# DiveComputer_TFT18.net
KiCad netlist of a schematic drawn in EAGLE
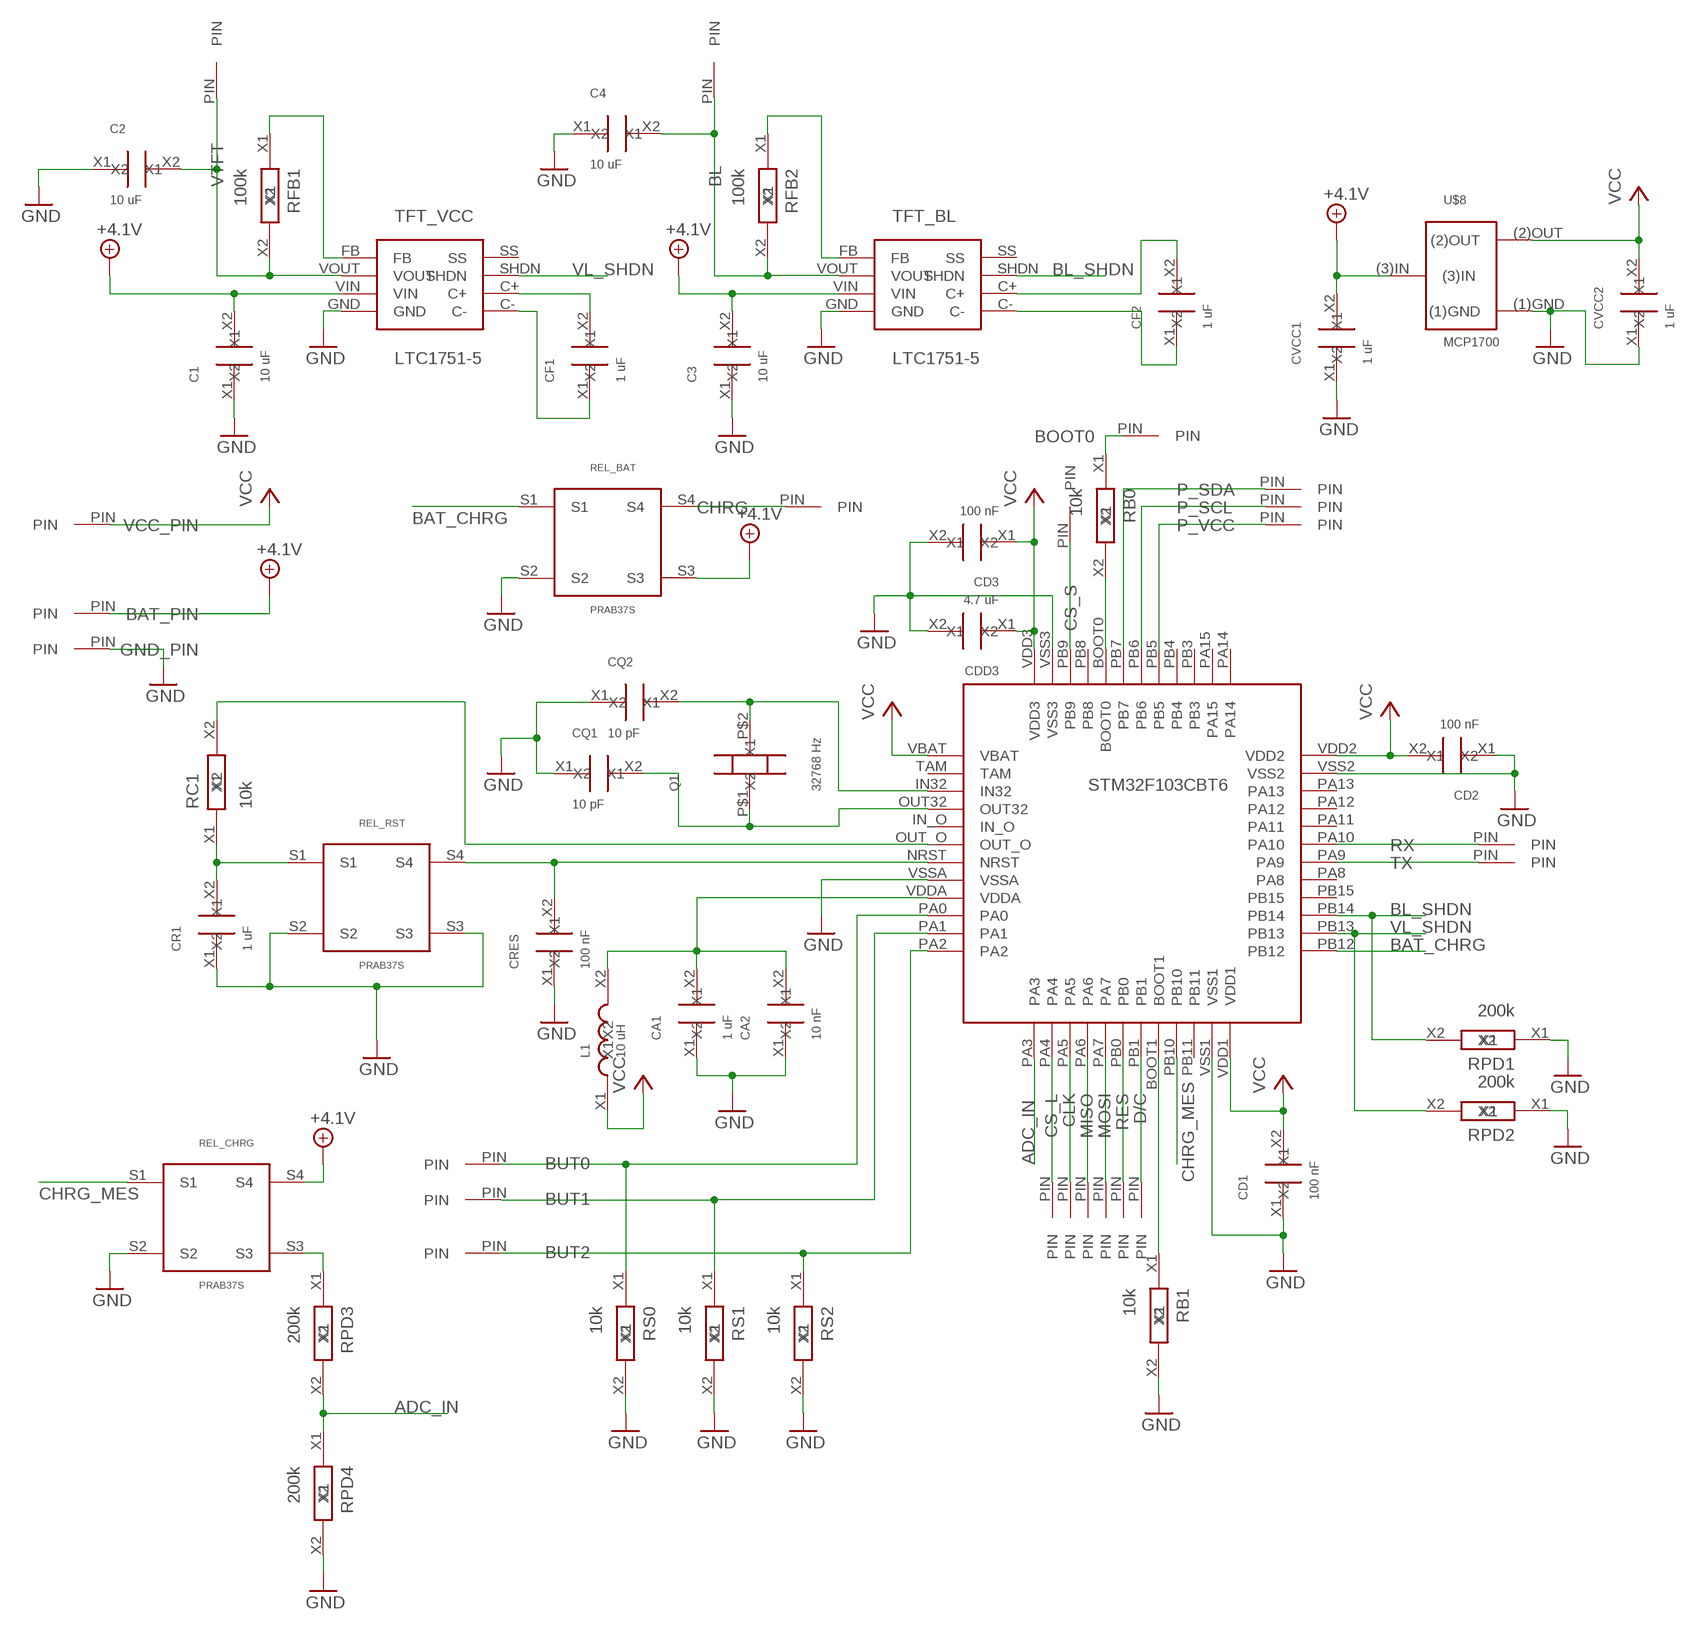
[diagram p0: schematic, sheet 1]

(export (version "E")
  (design (tool "Eeschema 10.0.6"))
  (components
    (comp (ref "BAT_PIN")
      (value "PIN_06")
      (footprint "eagle-import:PIN_06")
      (libsource (lib "eagle-import") (part "PIN_06"))
    )
    (comp (ref "BL")
      (value "PIN_06")
      (footprint "eagle-import:PIN_06")
      (libsource (lib "eagle-import") (part "PIN_06"))
    )
    (comp (ref "BOOT0")
      (value "PIN_06")
      (footprint "eagle-import:PIN_06")
      (libsource (lib "eagle-import") (part "PIN_06"))
    )
    (comp (ref "BUT0")
      (value "PIN_06")
      (footprint "eagle-import:PIN_06")
      (libsource (lib "eagle-import") (part "PIN_06"))
    )
    (comp (ref "BUT1")
      (value "PIN_06")
      (footprint "eagle-import:PIN_06")
      (libsource (lib "eagle-import") (part "PIN_06"))
    )
    (comp (ref "BUT2")
      (value "PIN_06")
      (footprint "eagle-import:PIN_06")
      (libsource (lib "eagle-import") (part "PIN_06"))
    )
    (comp (ref "C1")
      (value "10 uF")
      (footprint "eagle-import:SMD_2.1X1.25")
      (libsource (lib "eagle-import") (part "C_SMD_2.1X1.25"))
    )
    (comp (ref "C2")
      (value "10 uF")
      (footprint "eagle-import:SMD_2.1X1.25")
      (libsource (lib "eagle-import") (part "C_SMD_2.1X1.25"))
    )
    (comp (ref "C3")
      (value "10 uF")
      (footprint "eagle-import:SMD_2.1X1.25")
      (libsource (lib "eagle-import") (part "C_SMD_2.1X1.25"))
    )
    (comp (ref "C4")
      (value "10 uF")
      (footprint "eagle-import:SMD_2.1X1.25")
      (libsource (lib "eagle-import") (part "C_SMD_2.1X1.25"))
    )
    (comp (ref "CA1")
      (value "1 uF")
      (footprint "eagle-import:SMD_2.1X1.25")
      (libsource (lib "eagle-import") (part "C_SMD_2.1X1.25"))
    )
    (comp (ref "CA2")
      (value "10 nF")
      (footprint "eagle-import:SMD_2.1X1.25")
      (libsource (lib "eagle-import") (part "C_SMD_2.1X1.25"))
    )
    (comp (ref "CD1")
      (value "100 nF")
      (footprint "eagle-import:SMD_2.1X1.25")
      (libsource (lib "eagle-import") (part "C_SMD_2.1X1.25"))
    )
    (comp (ref "CD2")
      (value "100 nF")
      (footprint "eagle-import:SMD_2.1X1.25")
      (libsource (lib "eagle-import") (part "C_SMD_2.1X1.25"))
    )
    (comp (ref "CD3")
      (value "100 nF")
      (footprint "eagle-import:SMD_2.1X1.25")
      (libsource (lib "eagle-import") (part "C_SMD_2.1X1.25"))
    )
    (comp (ref "CDD3")
      (value "4.7 uF")
      (footprint "eagle-import:SMD_2.1X1.25")
      (libsource (lib "eagle-import") (part "C_SMD_2.1X1.25"))
    )
    (comp (ref "CF1")
      (value "1 uF")
      (footprint "eagle-import:SMD_2.1X1.25")
      (libsource (lib "eagle-import") (part "C_SMD_2.1X1.25"))
    )
    (comp (ref "CF2")
      (value "1 uF")
      (footprint "eagle-import:SMD_2.1X1.25")
      (libsource (lib "eagle-import") (part "C_SMD_2.1X1.25"))
    )
    (comp (ref "CHRG")
      (value "PIN_06")
      (footprint "eagle-import:PIN_06")
      (libsource (lib "eagle-import") (part "PIN_06"))
    )
    (comp (ref "CLK")
      (value "PIN_06")
      (footprint "eagle-import:PIN_06")
      (libsource (lib "eagle-import") (part "PIN_06"))
    )
    (comp (ref "CQ1")
      (value "10 pF")
      (footprint "eagle-import:SMD_2.1X1.25")
      (libsource (lib "eagle-import") (part "C_SMD_2.1X1.25"))
    )
    (comp (ref "CQ2")
      (value "10 pF")
      (footprint "eagle-import:SMD_2.1X1.25")
      (libsource (lib "eagle-import") (part "C_SMD_2.1X1.25"))
    )
    (comp (ref "CR1")
      (value "1 uF")
      (footprint "eagle-import:SMD_2.1X1.25")
      (libsource (lib "eagle-import") (part "C_SMD_2.1X1.25"))
    )
    (comp (ref "CRES")
      (value "100 nF")
      (footprint "eagle-import:SMD_2.1X1.25")
      (libsource (lib "eagle-import") (part "C_SMD_2.1X1.25"))
    )
    (comp (ref "CS_L")
      (value "PIN_06")
      (footprint "eagle-import:PIN_06")
      (libsource (lib "eagle-import") (part "PIN_06"))
    )
    (comp (ref "CS_S")
      (value "PIN_06")
      (footprint "eagle-import:PIN_06")
      (libsource (lib "eagle-import") (part "PIN_06"))
    )
    (comp (ref "CVCC1")
      (value "1 uF")
      (footprint "eagle-import:SMD_2.1X1.25")
      (libsource (lib "eagle-import") (part "C_SMD_2.1X1.25"))
    )
    (comp (ref "CVCC2")
      (value "1 uF")
      (footprint "eagle-import:SMD_2.1X1.25")
      (libsource (lib "eagle-import") (part "C_SMD_2.1X1.25"))
    )
    (comp (ref "D/C")
      (value "PIN_06")
      (footprint "eagle-import:PIN_06")
      (libsource (lib "eagle-import") (part "PIN_06"))
    )
    (comp (ref "GND_PIN")
      (value "PIN_06")
      (footprint "eagle-import:PIN_06")
      (libsource (lib "eagle-import") (part "PIN_06"))
    )
    (comp (ref "L1")
      (value "10 uH")
      (footprint "eagle-import:SMD_2.1X1.25")
      (libsource (lib "eagle-import") (part "L_SMD_2.1X1.25"))
    )
    (comp (ref "MISO")
      (value "PIN_06")
      (footprint "eagle-import:PIN_06")
      (libsource (lib "eagle-import") (part "PIN_06"))
    )
    (comp (ref "MOSI")
      (value "PIN_06")
      (footprint "eagle-import:PIN_06")
      (libsource (lib "eagle-import") (part "PIN_06"))
    )
    (comp (ref "P_SCL")
      (value "PIN_06")
      (footprint "eagle-import:PIN_06")
      (libsource (lib "eagle-import") (part "PIN_06"))
    )
    (comp (ref "P_SDA")
      (value "PIN_06")
      (footprint "eagle-import:PIN_06")
      (libsource (lib "eagle-import") (part "PIN_06"))
    )
    (comp (ref "P_VCC")
      (value "PIN_06")
      (footprint "eagle-import:PIN_06")
      (libsource (lib "eagle-import") (part "PIN_06"))
    )
    (comp (ref "Q1")
      (value "32768 Hz")
      (footprint "eagle-import:QUARTZ_CYL")
      (libsource (lib "eagle-import") (part "QUARTZ_CYL"))
    )
    (comp (ref "RB0")
      (value "10k")
      (footprint "eagle-import:SMD_2.1X1.25")
      (libsource (lib "eagle-import") (part "R_SMD_2.1X1.25"))
    )
    (comp (ref "RB1")
      (value "10k")
      (footprint "eagle-import:SMD_2.1X1.25")
      (libsource (lib "eagle-import") (part "R_SMD_2.1X1.25"))
    )
    (comp (ref "RC1")
      (value "10k")
      (footprint "eagle-import:SMD_2.1X1.25")
      (libsource (lib "eagle-import") (part "R_SMD_2.1X1.25"))
    )
    (comp (ref "REL_BAT")
      (value "PRAB37S")
      (footprint "eagle-import:PRAB37S")
      (libsource (lib "eagle-import") (part "PRAB37S"))
    )
    (comp (ref "REL_CHRG")
      (value "PRAB37S")
      (footprint "eagle-import:PRAB37S")
      (libsource (lib "eagle-import") (part "PRAB37S"))
    )
    (comp (ref "REL_RST")
      (value "PRAB37S")
      (footprint "eagle-import:PRAB37S")
      (libsource (lib "eagle-import") (part "PRAB37S"))
    )
    (comp (ref "RES")
      (value "PIN_06")
      (footprint "eagle-import:PIN_06")
      (libsource (lib "eagle-import") (part "PIN_06"))
    )
    (comp (ref "RFB1")
      (value "100k")
      (footprint "eagle-import:SMD_2.1X1.25")
      (libsource (lib "eagle-import") (part "R_SMD_2.1X1.25"))
    )
    (comp (ref "RFB2")
      (value "100k")
      (footprint "eagle-import:SMD_2.1X1.25")
      (libsource (lib "eagle-import") (part "R_SMD_2.1X1.25"))
    )
    (comp (ref "RPD1")
      (value "200k")
      (footprint "eagle-import:SMD_2.1X1.25")
      (libsource (lib "eagle-import") (part "R_SMD_2.1X1.25"))
    )
    (comp (ref "RPD2")
      (value "200k")
      (footprint "eagle-import:SMD_2.1X1.25")
      (libsource (lib "eagle-import") (part "R_SMD_2.1X1.25"))
    )
    (comp (ref "RPD3")
      (value "200k")
      (footprint "eagle-import:SMD_2.1X1.25")
      (libsource (lib "eagle-import") (part "R_SMD_2.1X1.25"))
    )
    (comp (ref "RPD4")
      (value "200k")
      (footprint "eagle-import:SMD_2.1X1.25")
      (libsource (lib "eagle-import") (part "R_SMD_2.1X1.25"))
    )
    (comp (ref "RS0")
      (value "10k")
      (footprint "eagle-import:SMD_2.1X1.25")
      (libsource (lib "eagle-import") (part "R_SMD_2.1X1.25"))
    )
    (comp (ref "RS1")
      (value "10k")
      (footprint "eagle-import:SMD_2.1X1.25")
      (libsource (lib "eagle-import") (part "R_SMD_2.1X1.25"))
    )
    (comp (ref "RS2")
      (value "10k")
      (footprint "eagle-import:SMD_2.1X1.25")
      (libsource (lib "eagle-import") (part "R_SMD_2.1X1.25"))
    )
    (comp (ref "RX")
      (value "PIN_06")
      (footprint "eagle-import:PIN_06")
      (libsource (lib "eagle-import") (part "PIN_06"))
    )
    (comp (ref "STM32F103CBT6")
      (value "STM32F103CBT6")
      (footprint "eagle-import:STM32F103CBT6")
      (libsource (lib "eagle-import") (part "STM32F103CBT6"))
    )
    (comp (ref "TFT_BL")
      (value "LTC1751-5")
      (footprint "eagle-import:LTC1751-5")
      (libsource (lib "eagle-import") (part "LTC1751-5"))
    )
    (comp (ref "TFT_VCC")
      (value "LTC1751-5")
      (footprint "eagle-import:LTC1751-5")
      (libsource (lib "eagle-import") (part "LTC1751-5"))
    )
    (comp (ref "TX")
      (value "PIN_06")
      (footprint "eagle-import:PIN_06")
      (libsource (lib "eagle-import") (part "PIN_06"))
    )
    (comp (ref "U$8")
      (value "MCP1700")
      (footprint "eagle-import:MCP1700")
      (libsource (lib "eagle-import") (part "MCP1700"))
    )
    (comp (ref "VCC_PIN")
      (value "PIN_06")
      (footprint "eagle-import:PIN_06")
      (libsource (lib "eagle-import") (part "PIN_06"))
    )
    (comp (ref "VTFT")
      (value "PIN_06")
      (footprint "eagle-import:PIN_06")
      (libsource (lib "eagle-import") (part "PIN_06"))
    )
  )
  (nets
    (net (code "1") (name "+4.1V") (class "Default")
      (node (ref "BAT_PIN") (pin "PIN") (pinfunction "PIN_PIN") (pintype "bidirectional"))
      (node (ref "C1") (pin "X2") (pinfunction "X2_X2") (pintype "bidirectional"))
      (node (ref "C3") (pin "X2") (pinfunction "X2_X2") (pintype "bidirectional"))
      (node (ref "CVCC1") (pin "X2") (pinfunction "X2_X2") (pintype "bidirectional"))
      (node (ref "REL_BAT") (pin "S3") (pinfunction "S3_S3") (pintype "bidirectional"))
      (node (ref "REL_CHRG") (pin "S4") (pinfunction "S4_S4") (pintype "bidirectional"))
      (node (ref "TFT_BL") (pin "VIN") (pinfunction "VIN_VIN") (pintype "bidirectional"))
      (node (ref "TFT_VCC") (pin "VIN") (pinfunction "VIN_VIN") (pintype "bidirectional"))
      (node (ref "U$8") (pin "(3)IN") (pinfunction "(3)IN_(3)IN") (pintype "bidirectional"))
    )
    (net (code "2") (name "/ADC_IN") (class "Default")
      (node (ref "RPD3") (pin "X2") (pinfunction "X2_X2") (pintype "bidirectional"))
      (node (ref "RPD4") (pin "X1") (pinfunction "X1_X1") (pintype "bidirectional"))
      (node (ref "STM32F103CBT6") (pin "PA3") (pinfunction "PA3_PA3") (pintype "bidirectional"))
    )
    (net (code "3") (name "/BAT_CHRG") (class "Default")
      (node (ref "REL_BAT") (pin "S1") (pinfunction "S1_S1") (pintype "bidirectional"))
      (node (ref "STM32F103CBT6") (pin "PB12") (pinfunction "PB12_PB12") (pintype "bidirectional"))
    )
    (net (code "4") (name "/BL_SHDN") (class "Default")
      (node (ref "RPD1") (pin "X2") (pinfunction "X2_X2") (pintype "bidirectional"))
      (node (ref "STM32F103CBT6") (pin "PB14") (pinfunction "PB14_PB14") (pintype "bidirectional"))
      (node (ref "TFT_BL") (pin "SHDN") (pinfunction "SHDN_SHDN") (pintype "bidirectional"))
    )
    (net (code "5") (name "/CHRG_MES") (class "Default")
      (node (ref "REL_CHRG") (pin "S1") (pinfunction "S1_S1") (pintype "bidirectional"))
      (node (ref "STM32F103CBT6") (pin "PB10") (pinfunction "PB10_PB10") (pintype "bidirectional"))
    )
    (net (code "6") (name "/VL_SHDN") (class "Default")
      (node (ref "RPD2") (pin "X2") (pinfunction "X2_X2") (pintype "bidirectional"))
      (node (ref "STM32F103CBT6") (pin "PB13") (pinfunction "PB13_PB13") (pintype "bidirectional"))
      (node (ref "TFT_VCC") (pin "SHDN") (pinfunction "SHDN_SHDN") (pintype "bidirectional"))
    )
    (net (code "7") (name "GND") (class "Default")
      (node (ref "C1") (pin "X1") (pinfunction "X1_X1") (pintype "bidirectional"))
      (node (ref "C2") (pin "X1") (pinfunction "X1_X1") (pintype "bidirectional"))
      (node (ref "C3") (pin "X1") (pinfunction "X1_X1") (pintype "bidirectional"))
      (node (ref "C4") (pin "X1") (pinfunction "X1_X1") (pintype "bidirectional"))
      (node (ref "CA1") (pin "X1") (pinfunction "X1_X1") (pintype "bidirectional"))
      (node (ref "CA2") (pin "X1") (pinfunction "X1_X1") (pintype "bidirectional"))
      (node (ref "CD1") (pin "X1") (pinfunction "X1_X1") (pintype "bidirectional"))
      (node (ref "CD2") (pin "X1") (pinfunction "X1_X1") (pintype "bidirectional"))
      (node (ref "CD3") (pin "X2") (pinfunction "X2_X2") (pintype "bidirectional"))
      (node (ref "CDD3") (pin "X2") (pinfunction "X2_X2") (pintype "bidirectional"))
      (node (ref "CQ1") (pin "X1") (pinfunction "X1_X1") (pintype "bidirectional"))
      (node (ref "CQ2") (pin "X1") (pinfunction "X1_X1") (pintype "bidirectional"))
      (node (ref "CR1") (pin "X1") (pinfunction "X1_X1") (pintype "bidirectional"))
      (node (ref "CRES") (pin "X1") (pinfunction "X1_X1") (pintype "bidirectional"))
      (node (ref "CVCC1") (pin "X1") (pinfunction "X1_X1") (pintype "bidirectional"))
      (node (ref "CVCC2") (pin "X1") (pinfunction "X1_X1") (pintype "bidirectional"))
      (node (ref "GND_PIN") (pin "PIN") (pinfunction "PIN_PIN") (pintype "bidirectional"))
      (node (ref "RB1") (pin "X2") (pinfunction "X2_X2") (pintype "bidirectional"))
      (node (ref "REL_BAT") (pin "S2") (pinfunction "S2_S2") (pintype "bidirectional"))
      (node (ref "REL_CHRG") (pin "S2") (pinfunction "S2_S2") (pintype "bidirectional"))
      (node (ref "REL_RST") (pin "S2") (pinfunction "S2_S2") (pintype "bidirectional"))
      (node (ref "REL_RST") (pin "S3") (pinfunction "S3_S3") (pintype "bidirectional"))
      (node (ref "RPD1") (pin "X1") (pinfunction "X1_X1") (pintype "bidirectional"))
      (node (ref "RPD2") (pin "X1") (pinfunction "X1_X1") (pintype "bidirectional"))
      (node (ref "RPD4") (pin "X2") (pinfunction "X2_X2") (pintype "bidirectional"))
      (node (ref "RS0") (pin "X2") (pinfunction "X2_X2") (pintype "bidirectional"))
      (node (ref "RS1") (pin "X2") (pinfunction "X2_X2") (pintype "bidirectional"))
      (node (ref "RS2") (pin "X2") (pinfunction "X2_X2") (pintype "bidirectional"))
      (node (ref "STM32F103CBT6") (pin "VSS1") (pinfunction "VSS1_VSS1") (pintype "bidirectional"))
      (node (ref "STM32F103CBT6") (pin "VSS2") (pinfunction "VSS2_VSS2") (pintype "bidirectional"))
      (node (ref "STM32F103CBT6") (pin "VSS3") (pinfunction "VSS3_VSS3") (pintype "bidirectional"))
      (node (ref "STM32F103CBT6") (pin "VSSA") (pinfunction "VSSA_VSSA") (pintype "bidirectional"))
      (node (ref "TFT_BL") (pin "GND") (pinfunction "GND_GND") (pintype "bidirectional"))
      (node (ref "TFT_VCC") (pin "GND") (pinfunction "GND_GND") (pintype "bidirectional"))
      (node (ref "U$8") (pin "(1)GND") (pinfunction "(1)GND_(1)GND") (pintype "bidirectional"))
    )
    (net (code "8") (name "Net-(BL-PadPIN)") (class "Default")
      (node (ref "BL") (pin "PIN") (pinfunction "PIN_PIN") (pintype "bidirectional"))
      (node (ref "C4") (pin "X2") (pinfunction "X2_X2") (pintype "bidirectional"))
      (node (ref "RFB2") (pin "X2") (pinfunction "X2_X2") (pintype "bidirectional"))
      (node (ref "TFT_BL") (pin "VOUT") (pinfunction "VOUT_VOUT") (pintype "bidirectional"))
    )
    (net (code "9") (name "Net-(BOOT0-PadPIN)") (class "Default")
      (node (ref "BOOT0") (pin "PIN") (pinfunction "PIN_PIN") (pintype "bidirectional"))
      (node (ref "RB0") (pin "X1") (pinfunction "X1_X1") (pintype "bidirectional"))
    )
    (net (code "10") (name "Net-(BUT0-PadPIN)") (class "Default")
      (node (ref "BUT0") (pin "PIN") (pinfunction "PIN_PIN") (pintype "bidirectional"))
      (node (ref "RS0") (pin "X1") (pinfunction "X1_X1") (pintype "bidirectional"))
      (node (ref "STM32F103CBT6") (pin "PA0") (pinfunction "PA0_PA0") (pintype "bidirectional"))
    )
    (net (code "11") (name "Net-(BUT1-PadPIN)") (class "Default")
      (node (ref "BUT1") (pin "PIN") (pinfunction "PIN_PIN") (pintype "bidirectional"))
      (node (ref "RS1") (pin "X1") (pinfunction "X1_X1") (pintype "bidirectional"))
      (node (ref "STM32F103CBT6") (pin "PA1") (pinfunction "PA1_PA1") (pintype "bidirectional"))
    )
    (net (code "12") (name "Net-(BUT2-PadPIN)") (class "Default")
      (node (ref "BUT2") (pin "PIN") (pinfunction "PIN_PIN") (pintype "bidirectional"))
      (node (ref "RS2") (pin "X1") (pinfunction "X1_X1") (pintype "bidirectional"))
      (node (ref "STM32F103CBT6") (pin "PA2") (pinfunction "PA2_PA2") (pintype "bidirectional"))
    )
    (net (code "13") (name "Net-(C2-PadX2)") (class "Default")
      (node (ref "C2") (pin "X2") (pinfunction "X2_X2") (pintype "bidirectional"))
      (node (ref "RFB1") (pin "X2") (pinfunction "X2_X2") (pintype "bidirectional"))
      (node (ref "TFT_VCC") (pin "VOUT") (pinfunction "VOUT_VOUT") (pintype "bidirectional"))
      (node (ref "VTFT") (pin "PIN") (pinfunction "PIN_PIN") (pintype "bidirectional"))
    )
    (net (code "14") (name "Net-(CA1-PadX2)") (class "Default")
      (node (ref "CA1") (pin "X2") (pinfunction "X2_X2") (pintype "bidirectional"))
      (node (ref "CA2") (pin "X2") (pinfunction "X2_X2") (pintype "bidirectional"))
      (node (ref "L1") (pin "X2") (pinfunction "X2_X2") (pintype "bidirectional"))
      (node (ref "STM32F103CBT6") (pin "VDDA") (pinfunction "VDDA_VDDA") (pintype "bidirectional"))
    )
    (net (code "15") (name "Net-(CF1-PadX1)") (class "Default")
      (node (ref "CF1") (pin "X1") (pinfunction "X1_X1") (pintype "bidirectional"))
      (node (ref "TFT_VCC") (pin "C-") (pinfunction "C-_C-") (pintype "bidirectional"))
    )
    (net (code "16") (name "Net-(CF1-PadX2)") (class "Default")
      (node (ref "CF1") (pin "X2") (pinfunction "X2_X2") (pintype "bidirectional"))
      (node (ref "TFT_VCC") (pin "C+") (pinfunction "C+_C+") (pintype "bidirectional"))
    )
    (net (code "17") (name "Net-(CF2-PadX1)") (class "Default")
      (node (ref "CF2") (pin "X1") (pinfunction "X1_X1") (pintype "bidirectional"))
      (node (ref "TFT_BL") (pin "C-") (pinfunction "C-_C-") (pintype "bidirectional"))
    )
    (net (code "18") (name "Net-(CF2-PadX2)") (class "Default")
      (node (ref "CF2") (pin "X2") (pinfunction "X2_X2") (pintype "bidirectional"))
      (node (ref "TFT_BL") (pin "C+") (pinfunction "C+_C+") (pintype "bidirectional"))
    )
    (net (code "19") (name "Net-(CHRG-PadPIN)") (class "Default")
      (node (ref "CHRG") (pin "PIN") (pinfunction "PIN_PIN") (pintype "bidirectional"))
      (node (ref "REL_BAT") (pin "S4") (pinfunction "S4_S4") (pintype "bidirectional"))
    )
    (net (code "20") (name "Net-(CLK-PadPIN)") (class "Default")
      (node (ref "CLK") (pin "PIN") (pinfunction "PIN_PIN") (pintype "bidirectional"))
      (node (ref "STM32F103CBT6") (pin "PA5") (pinfunction "PA5_PA5") (pintype "bidirectional"))
    )
    (net (code "21") (name "Net-(CR1-PadX2)") (class "Default")
      (node (ref "CR1") (pin "X2") (pinfunction "X2_X2") (pintype "bidirectional"))
      (node (ref "RC1") (pin "X1") (pinfunction "X1_X1") (pintype "bidirectional"))
      (node (ref "REL_RST") (pin "S1") (pinfunction "S1_S1") (pintype "bidirectional"))
    )
    (net (code "22") (name "Net-(CRES-PadX2)") (class "Default")
      (node (ref "CRES") (pin "X2") (pinfunction "X2_X2") (pintype "bidirectional"))
      (node (ref "REL_RST") (pin "S4") (pinfunction "S4_S4") (pintype "bidirectional"))
      (node (ref "STM32F103CBT6") (pin "NRST") (pinfunction "NRST_NRST") (pintype "bidirectional"))
    )
    (net (code "23") (name "Net-(CS_L-PadPIN)") (class "Default")
      (node (ref "CS_L") (pin "PIN") (pinfunction "PIN_PIN") (pintype "bidirectional"))
      (node (ref "STM32F103CBT6") (pin "PA4") (pinfunction "PA4_PA4") (pintype "bidirectional"))
    )
    (net (code "24") (name "Net-(CS_S-PadPIN)") (class "Default")
      (node (ref "CS_S") (pin "PIN") (pinfunction "PIN_PIN") (pintype "bidirectional"))
      (node (ref "STM32F103CBT6") (pin "PB9") (pinfunction "PB9_PB9") (pintype "bidirectional"))
    )
    (net (code "25") (name "Net-(D/C-PadPIN)") (class "Default")
      (node (ref "D/C") (pin "PIN") (pinfunction "PIN_PIN") (pintype "bidirectional"))
      (node (ref "STM32F103CBT6") (pin "PB1") (pinfunction "PB1_PB1") (pintype "bidirectional"))
    )
    (net (code "26") (name "Net-(MISO-PadPIN)") (class "Default")
      (node (ref "MISO") (pin "PIN") (pinfunction "PIN_PIN") (pintype "bidirectional"))
      (node (ref "STM32F103CBT6") (pin "PA6") (pinfunction "PA6_PA6") (pintype "bidirectional"))
    )
    (net (code "27") (name "Net-(MOSI-PadPIN)") (class "Default")
      (node (ref "MOSI") (pin "PIN") (pinfunction "PIN_PIN") (pintype "bidirectional"))
      (node (ref "STM32F103CBT6") (pin "PA7") (pinfunction "PA7_PA7") (pintype "bidirectional"))
    )
    (net (code "28") (name "Net-(P_SCL-PadPIN)") (class "Default")
      (node (ref "P_SCL") (pin "PIN") (pinfunction "PIN_PIN") (pintype "bidirectional"))
      (node (ref "STM32F103CBT6") (pin "PB6") (pinfunction "PB6_PB6") (pintype "bidirectional"))
    )
    (net (code "29") (name "Net-(P_SDA-PadPIN)") (class "Default")
      (node (ref "P_SDA") (pin "PIN") (pinfunction "PIN_PIN") (pintype "bidirectional"))
      (node (ref "STM32F103CBT6") (pin "PB7") (pinfunction "PB7_PB7") (pintype "bidirectional"))
    )
    (net (code "30") (name "Net-(P_VCC-PadPIN)") (class "Default")
      (node (ref "P_VCC") (pin "PIN") (pinfunction "PIN_PIN") (pintype "bidirectional"))
      (node (ref "STM32F103CBT6") (pin "PB5") (pinfunction "PB5_PB5") (pintype "bidirectional"))
    )
    (net (code "31") (name "Net-(Q1-X1)") (class "Default")
      (node (ref "CQ1") (pin "X2") (pinfunction "X2_X2") (pintype "bidirectional"))
      (node (ref "Q1") (pin "P$1") (pinfunction "X1_P$1") (pintype "bidirectional"))
      (node (ref "STM32F103CBT6") (pin "OUT32") (pinfunction "OUT32_OUT32") (pintype "bidirectional"))
    )
    (net (code "32") (name "Net-(Q1-X2)") (class "Default")
      (node (ref "CQ2") (pin "X2") (pinfunction "X2_X2") (pintype "bidirectional"))
      (node (ref "Q1") (pin "P$2") (pinfunction "X2_P$2") (pintype "bidirectional"))
      (node (ref "STM32F103CBT6") (pin "IN32") (pinfunction "IN32_IN32") (pintype "bidirectional"))
    )
    (net (code "33") (name "Net-(RB0-PadX2)") (class "Default")
      (node (ref "RB0") (pin "X2") (pinfunction "X2_X2") (pintype "bidirectional"))
      (node (ref "STM32F103CBT6") (pin "BOOT0") (pinfunction "BOOT0_BOOT0") (pintype "bidirectional"))
    )
    (net (code "34") (name "Net-(RB1-PadX1)") (class "Default")
      (node (ref "RB1") (pin "X1") (pinfunction "X1_X1") (pintype "bidirectional"))
      (node (ref "STM32F103CBT6") (pin "BOOT1") (pinfunction "BOOT1_BOOT1") (pintype "bidirectional"))
    )
    (net (code "35") (name "Net-(RC1-PadX2)") (class "Default")
      (node (ref "RC1") (pin "X2") (pinfunction "X2_X2") (pintype "bidirectional"))
      (node (ref "STM32F103CBT6") (pin "OUT_O") (pinfunction "OUT_O_OUT_O") (pintype "bidirectional"))
    )
    (net (code "36") (name "Net-(REL_CHRG-PadS3)") (class "Default")
      (node (ref "REL_CHRG") (pin "S3") (pinfunction "S3_S3") (pintype "bidirectional"))
      (node (ref "RPD3") (pin "X1") (pinfunction "X1_X1") (pintype "bidirectional"))
    )
    (net (code "37") (name "Net-(RES-PadPIN)") (class "Default")
      (node (ref "RES") (pin "PIN") (pinfunction "PIN_PIN") (pintype "bidirectional"))
      (node (ref "STM32F103CBT6") (pin "PB0") (pinfunction "PB0_PB0") (pintype "bidirectional"))
    )
    (net (code "38") (name "Net-(RFB1-PadX1)") (class "Default")
      (node (ref "RFB1") (pin "X1") (pinfunction "X1_X1") (pintype "bidirectional"))
      (node (ref "TFT_VCC") (pin "FB") (pinfunction "FB_FB") (pintype "bidirectional"))
    )
    (net (code "39") (name "Net-(RFB2-PadX1)") (class "Default")
      (node (ref "RFB2") (pin "X1") (pinfunction "X1_X1") (pintype "bidirectional"))
      (node (ref "TFT_BL") (pin "FB") (pinfunction "FB_FB") (pintype "bidirectional"))
    )
    (net (code "40") (name "Net-(RX-PadPIN)") (class "Default")
      (node (ref "RX") (pin "PIN") (pinfunction "PIN_PIN") (pintype "bidirectional"))
      (node (ref "STM32F103CBT6") (pin "PA10") (pinfunction "PA10_PA10") (pintype "bidirectional"))
    )
    (net (code "41") (name "Net-(STM32F103CBT6-PadPA9)") (class "Default")
      (node (ref "STM32F103CBT6") (pin "PA9") (pinfunction "PA9_PA9") (pintype "bidirectional"))
      (node (ref "TX") (pin "PIN") (pinfunction "PIN_PIN") (pintype "bidirectional"))
    )
    (net (code "42") (name "VCC") (class "Default")
      (node (ref "CD1") (pin "X2") (pinfunction "X2_X2") (pintype "bidirectional"))
      (node (ref "CD2") (pin "X2") (pinfunction "X2_X2") (pintype "bidirectional"))
      (node (ref "CD3") (pin "X1") (pinfunction "X1_X1") (pintype "bidirectional"))
      (node (ref "CDD3") (pin "X1") (pinfunction "X1_X1") (pintype "bidirectional"))
      (node (ref "CVCC2") (pin "X2") (pinfunction "X2_X2") (pintype "bidirectional"))
      (node (ref "L1") (pin "X1") (pinfunction "X1_X1") (pintype "bidirectional"))
      (node (ref "STM32F103CBT6") (pin "VBAT") (pinfunction "VBAT_VBAT") (pintype "bidirectional"))
      (node (ref "STM32F103CBT6") (pin "VDD1") (pinfunction "VDD1_VDD1") (pintype "bidirectional"))
      (node (ref "STM32F103CBT6") (pin "VDD2") (pinfunction "VDD2_VDD2") (pintype "bidirectional"))
      (node (ref "STM32F103CBT6") (pin "VDD3") (pinfunction "VDD3_VDD3") (pintype "bidirectional"))
      (node (ref "U$8") (pin "(2)OUT") (pinfunction "(2)OUT_(2)OUT") (pintype "bidirectional"))
      (node (ref "VCC_PIN") (pin "PIN") (pinfunction "PIN_PIN") (pintype "bidirectional"))
    )
    (net (code "43") (name "unconnected-(STM32F103CBT6-PadIN_O)") (class "Default")
      (node (ref "STM32F103CBT6") (pin "IN_O") (pinfunction "IN_O_IN_O") (pintype "bidirectional"))
    )
    (net (code "44") (name "unconnected-(STM32F103CBT6-PadPA8)") (class "Default")
      (node (ref "STM32F103CBT6") (pin "PA8") (pinfunction "PA8_PA8") (pintype "bidirectional"))
    )
    (net (code "45") (name "unconnected-(STM32F103CBT6-PadPA11)") (class "Default")
      (node (ref "STM32F103CBT6") (pin "PA11") (pinfunction "PA11_PA11") (pintype "bidirectional"))
    )
    (net (code "46") (name "unconnected-(STM32F103CBT6-PadPA12)") (class "Default")
      (node (ref "STM32F103CBT6") (pin "PA12") (pinfunction "PA12_PA12") (pintype "bidirectional"))
    )
    (net (code "47") (name "unconnected-(STM32F103CBT6-PadPA13)") (class "Default")
      (node (ref "STM32F103CBT6") (pin "PA13") (pinfunction "PA13_PA13") (pintype "bidirectional"))
    )
    (net (code "48") (name "unconnected-(STM32F103CBT6-PadPA14)") (class "Default")
      (node (ref "STM32F103CBT6") (pin "PA14") (pinfunction "PA14_PA14") (pintype "bidirectional"))
    )
    (net (code "49") (name "unconnected-(STM32F103CBT6-PadPA15)") (class "Default")
      (node (ref "STM32F103CBT6") (pin "PA15") (pinfunction "PA15_PA15") (pintype "bidirectional"))
    )
    (net (code "50") (name "unconnected-(STM32F103CBT6-PadPB3)") (class "Default")
      (node (ref "STM32F103CBT6") (pin "PB3") (pinfunction "PB3_PB3") (pintype "bidirectional"))
    )
    (net (code "51") (name "unconnected-(STM32F103CBT6-PadPB4)") (class "Default")
      (node (ref "STM32F103CBT6") (pin "PB4") (pinfunction "PB4_PB4") (pintype "bidirectional"))
    )
    (net (code "52") (name "unconnected-(STM32F103CBT6-PadPB8)") (class "Default")
      (node (ref "STM32F103CBT6") (pin "PB8") (pinfunction "PB8_PB8") (pintype "bidirectional"))
    )
    (net (code "53") (name "unconnected-(STM32F103CBT6-PadPB11)") (class "Default")
      (node (ref "STM32F103CBT6") (pin "PB11") (pinfunction "PB11_PB11") (pintype "bidirectional"))
    )
    (net (code "54") (name "unconnected-(STM32F103CBT6-PadPB15)") (class "Default")
      (node (ref "STM32F103CBT6") (pin "PB15") (pinfunction "PB15_PB15") (pintype "bidirectional"))
    )
    (net (code "55") (name "unconnected-(STM32F103CBT6-PadTAM)") (class "Default")
      (node (ref "STM32F103CBT6") (pin "TAM") (pinfunction "TAM_TAM") (pintype "bidirectional"))
    )
    (net (code "56") (name "unconnected-(TFT_BL-PadSS)") (class "Default")
      (node (ref "TFT_BL") (pin "SS") (pinfunction "SS_SS") (pintype "bidirectional"))
    )
    (net (code "57") (name "unconnected-(TFT_VCC-PadSS)") (class "Default")
      (node (ref "TFT_VCC") (pin "SS") (pinfunction "SS_SS") (pintype "bidirectional"))
    )
  )
)
